# tap_test.net
KiCad netlist of a schematic drawn in EAGLE
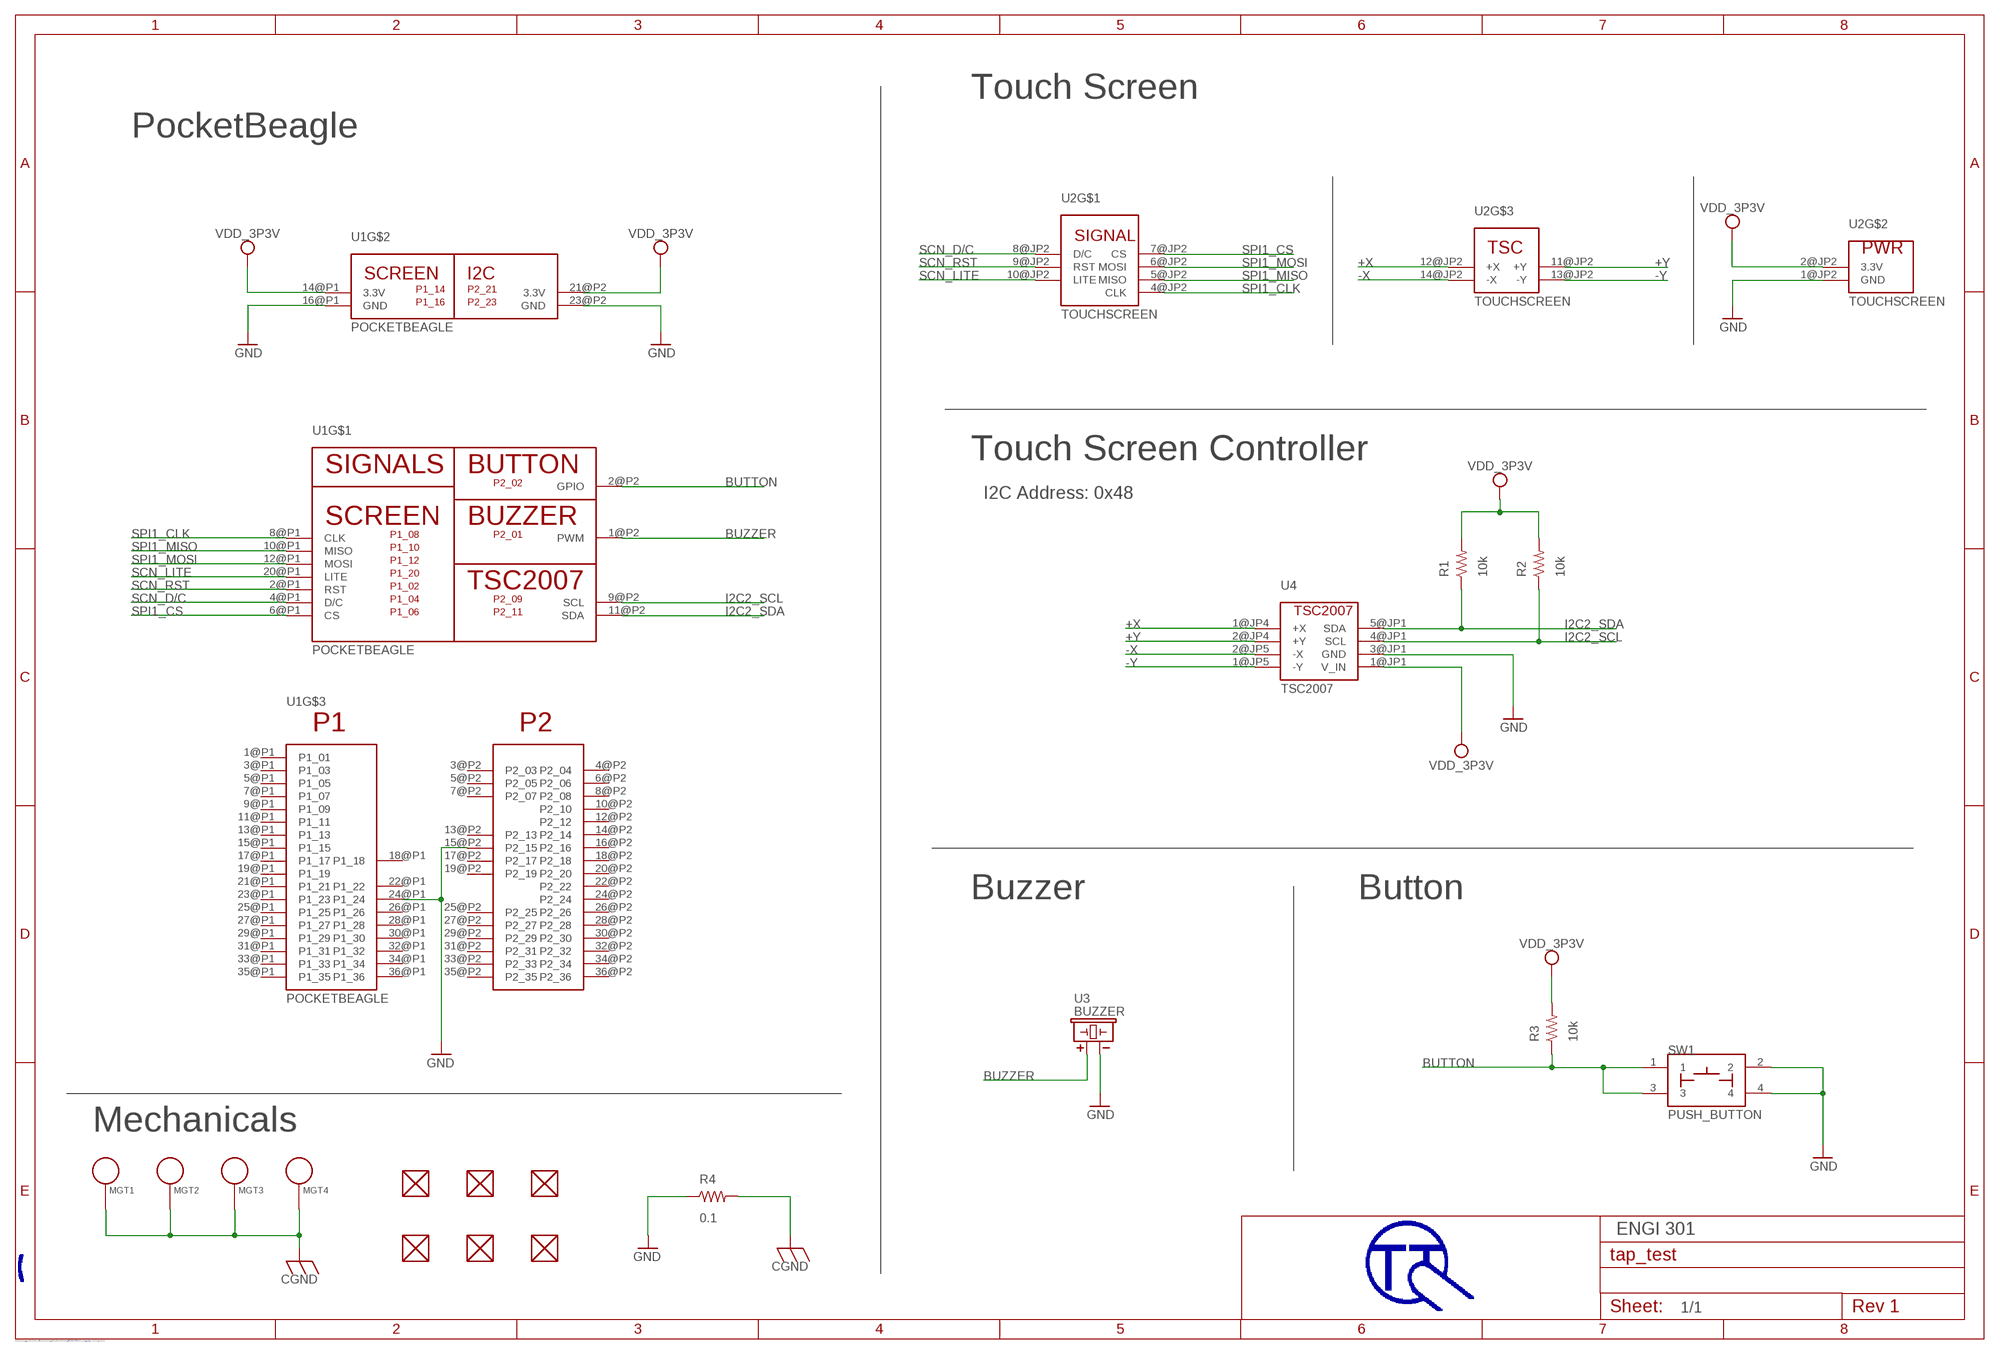
[diagram p0: schematic, sheet 1]

(export (version "E")
  (design (tool "Eeschema 10.0.6"))
  (components
    (comp (ref "FUD1")
      (value "FIDUCIAL")
      (footprint "eagle-import:FIDUCIAL_40MIL")
      (libsource (lib "eagle-import") (part "FIDUCIAL"))
    )
    (comp (ref "FUD2")
      (value "FIDUCIAL")
      (footprint "eagle-import:FIDUCIAL_40MIL")
      (libsource (lib "eagle-import") (part "FIDUCIAL"))
    )
    (comp (ref "FUD3")
      (value "FIDUCIAL")
      (footprint "eagle-import:FIDUCIAL_40MIL")
      (libsource (lib "eagle-import") (part "FIDUCIAL"))
    )
    (comp (ref "FUD4")
      (value "FIDUCIAL")
      (footprint "eagle-import:FIDUCIAL_40MIL")
      (libsource (lib "eagle-import") (part "FIDUCIAL"))
    )
    (comp (ref "FUD5")
      (value "FIDUCIAL")
      (footprint "eagle-import:FIDUCIAL_40MIL")
      (libsource (lib "eagle-import") (part "FIDUCIAL"))
    )
    (comp (ref "FUD6")
      (value "FIDUCIAL")
      (footprint "eagle-import:FIDUCIAL_40MIL")
      (libsource (lib "eagle-import") (part "FIDUCIAL"))
    )
    (comp (ref "MGT1")
      (value "MOUNTING_HOLE")
      (footprint "eagle-import:MOUNTING_HOLE")
      (libsource (lib "eagle-import") (part "MOUNTING_HOLE"))
    )
    (comp (ref "MGT2")
      (value "MOUNTING_HOLE")
      (footprint "eagle-import:MOUNTING_HOLE")
      (libsource (lib "eagle-import") (part "MOUNTING_HOLE"))
    )
    (comp (ref "MGT3")
      (value "MOUNTING_HOLE")
      (footprint "eagle-import:MOUNTING_HOLE")
      (libsource (lib "eagle-import") (part "MOUNTING_HOLE"))
    )
    (comp (ref "MGT4")
      (value "MOUNTING_HOLE")
      (footprint "eagle-import:MOUNTING_HOLE")
      (libsource (lib "eagle-import") (part "MOUNTING_HOLE"))
    )
    (comp (ref "R1")
      (value "10k")
      (footprint "eagle-import:R0603")
      (libsource (lib "eagle-import") (part "R_R0603"))
    )
    (comp (ref "R2")
      (value "10k")
      (footprint "eagle-import:R0603")
      (libsource (lib "eagle-import") (part "R_R0603"))
    )
    (comp (ref "R3")
      (value "10k")
      (footprint "eagle-import:R0603")
      (libsource (lib "eagle-import") (part "R_R0603"))
    )
    (comp (ref "R4")
      (value "0.1")
      (footprint "eagle-import:R0603")
      (libsource (lib "eagle-import") (part "R_R0603"))
    )
    (comp (ref "SW1")
      (value "PUSH_BUTTON")
      (footprint "eagle-import:BUTTON_12.5MM")
      (libsource (lib "eagle-import") (part "PUSH_BUTTON"))
    )
    (comp (ref "U1")
      (value "POCKETBEAGLE")
      (footprint "eagle-import:POCKETBEAGLE")
      (libsource (lib "eagle-import") (part "POCKETBEAGLE"))
    )
    (comp (ref "U2")
      (value "TOUCHSCREEN")
      (footprint "eagle-import:TOUCHSCREEN")
      (libsource (lib "eagle-import") (part "TOUCHSCREEN"))
    )
    (comp (ref "U3")
      (value "BUZZER")
      (footprint "eagle-import:BUZZER_6.5MM")
      (libsource (lib "eagle-import") (part "BUZZER"))
    )
    (comp (ref "U4")
      (value "TSC2007")
      (footprint "eagle-import:TSC2007")
      (libsource (lib "eagle-import") (part "TSC2007"))
    )
  )
  (nets
    (net (code "1") (name "/+X") (class "Default")
      (node (ref "U2") (pin "12@JP2") (pinfunction "+X_12@JP2") (pintype "bidirectional"))
      (node (ref "U4") (pin "1@JP4") (pinfunction "+X_1@JP4") (pintype "bidirectional"))
    )
    (net (code "2") (name "/+Y") (class "Default")
      (node (ref "U2") (pin "11@JP2") (pinfunction "+Y_11@JP2") (pintype "bidirectional"))
      (node (ref "U4") (pin "2@JP4") (pinfunction "+Y_2@JP4") (pintype "bidirectional"))
    )
    (net (code "3") (name "/-X") (class "Default")
      (node (ref "U2") (pin "14@JP2") (pinfunction "-X_14@JP2") (pintype "bidirectional"))
      (node (ref "U4") (pin "2@JP5") (pinfunction "-X_2@JP5") (pintype "bidirectional"))
    )
    (net (code "4") (name "/-Y") (class "Default")
      (node (ref "U2") (pin "13@JP2") (pinfunction "-Y_13@JP2") (pintype "bidirectional"))
      (node (ref "U4") (pin "1@JP5") (pinfunction "-Y_1@JP5") (pintype "bidirectional"))
    )
    (net (code "5") (name "/BUTTON") (class "Default")
      (node (ref "R3") (pin "1") (pinfunction "1_1") (pintype "passive"))
      (node (ref "SW1") (pin "1") (pinfunction "1_1") (pintype "bidirectional"))
      (node (ref "SW1") (pin "3") (pinfunction "3_3") (pintype "bidirectional"))
      (node (ref "U1") (pin "2@P2") (pinfunction "GPIO_2@P2") (pintype "bidirectional"))
    )
    (net (code "6") (name "/BUZZER") (class "Default")
      (node (ref "U1") (pin "1@P2") (pinfunction "PWM_1@P2") (pintype "bidirectional"))
      (node (ref "U3") (pin "+") (pinfunction "+_+") (pintype "passive"))
    )
    (net (code "7") (name "/I2C2_SCL") (class "Default")
      (node (ref "R2") (pin "1") (pinfunction "1_1") (pintype "passive"))
      (node (ref "U1") (pin "9@P2") (pinfunction "SCL_9@P2") (pintype "bidirectional"))
      (node (ref "U4") (pin "4@JP1") (pinfunction "SCL_4@JP1") (pintype "bidirectional"))
    )
    (net (code "8") (name "/I2C2_SDA") (class "Default")
      (node (ref "R1") (pin "1") (pinfunction "1_1") (pintype "passive"))
      (node (ref "U1") (pin "11@P2") (pinfunction "SDA_11@P2") (pintype "bidirectional"))
      (node (ref "U4") (pin "5@JP1") (pinfunction "SDA_5@JP1") (pintype "bidirectional"))
    )
    (net (code "9") (name "/SCN_D{slash}C") (class "Default")
      (node (ref "U1") (pin "4@P1") (pinfunction "D/C_4@P1") (pintype "bidirectional"))
      (node (ref "U2") (pin "8@JP2") (pinfunction "D/C_8@JP2") (pintype "bidirectional"))
    )
    (net (code "10") (name "/SCN_LITE") (class "Default")
      (node (ref "U1") (pin "20@P1") (pinfunction "LITE_20@P1") (pintype "bidirectional"))
      (node (ref "U2") (pin "10@JP2") (pinfunction "LITE_10@JP2") (pintype "bidirectional"))
    )
    (net (code "11") (name "/SCN_RST") (class "Default")
      (node (ref "U1") (pin "2@P1") (pinfunction "RST_2@P1") (pintype "bidirectional"))
      (node (ref "U2") (pin "9@JP2") (pinfunction "RST_9@JP2") (pintype "bidirectional"))
    )
    (net (code "12") (name "/SPI1_CLK") (class "Default")
      (node (ref "U1") (pin "8@P1") (pinfunction "CLK_8@P1") (pintype "bidirectional"))
      (node (ref "U2") (pin "4@JP2") (pinfunction "CLK_4@JP2") (pintype "bidirectional"))
    )
    (net (code "13") (name "/SPI1_CS") (class "Default")
      (node (ref "U1") (pin "6@P1") (pinfunction "CS_6@P1") (pintype "bidirectional"))
      (node (ref "U2") (pin "7@JP2") (pinfunction "CS_7@JP2") (pintype "bidirectional"))
    )
    (net (code "14") (name "/SPI1_MISO") (class "Default")
      (node (ref "U1") (pin "10@P1") (pinfunction "MISO_10@P1") (pintype "bidirectional"))
      (node (ref "U2") (pin "5@JP2") (pinfunction "MISO_5@JP2") (pintype "bidirectional"))
    )
    (net (code "15") (name "/SPI1_MOSI") (class "Default")
      (node (ref "U1") (pin "12@P1") (pinfunction "MOSI_12@P1") (pintype "bidirectional"))
      (node (ref "U2") (pin "6@JP2") (pinfunction "MOSI_6@JP2") (pintype "bidirectional"))
    )
    (net (code "16") (name "CGND") (class "Default")
      (node (ref "MGT1") (pin "P$1") (pinfunction "P$1_P$1") (pintype "bidirectional"))
      (node (ref "MGT2") (pin "P$1") (pinfunction "P$1_P$1") (pintype "bidirectional"))
      (node (ref "MGT3") (pin "P$1") (pinfunction "P$1_P$1") (pintype "bidirectional"))
      (node (ref "MGT4") (pin "P$1") (pinfunction "P$1_P$1") (pintype "bidirectional"))
      (node (ref "R4") (pin "2") (pinfunction "2_2") (pintype "passive"))
    )
    (net (code "17") (name "GND") (class "Default")
      (node (ref "R4") (pin "1") (pinfunction "1_1") (pintype "passive"))
      (node (ref "SW1") (pin "2") (pinfunction "2_2") (pintype "bidirectional"))
      (node (ref "SW1") (pin "4") (pinfunction "4_4") (pintype "bidirectional"))
      (node (ref "U1") (pin "15@P2") (pinfunction "P2_15_15@P2") (pintype "bidirectional"))
      (node (ref "U1") (pin "16@P1") (pinfunction "GND_16@P1") (pintype "bidirectional"))
      (node (ref "U1") (pin "23@P2") (pinfunction "GND_23@P2") (pintype "bidirectional"))
      (node (ref "U1") (pin "24@P1") (pinfunction "P1_24_24@P1") (pintype "bidirectional"))
      (node (ref "U2") (pin "1@JP2") (pinfunction "GND_1@JP2") (pintype "bidirectional"))
      (node (ref "U3") (pin "-") (pinfunction "-_-") (pintype "passive"))
      (node (ref "U4") (pin "3@JP1") (pinfunction "GND_3@JP1") (pintype "bidirectional"))
    )
    (net (code "18") (name "VDD_3P3V") (class "Default")
      (node (ref "R1") (pin "2") (pinfunction "2_2") (pintype "passive"))
      (node (ref "R2") (pin "2") (pinfunction "2_2") (pintype "passive"))
      (node (ref "R3") (pin "2") (pinfunction "2_2") (pintype "passive"))
      (node (ref "U1") (pin "14@P1") (pinfunction "3.3V_14@P1") (pintype "bidirectional"))
      (node (ref "U1") (pin "21@P2") (pinfunction "3.3V_21@P2") (pintype "bidirectional"))
      (node (ref "U2") (pin "2@JP2") (pinfunction "3.3V_2@JP2") (pintype "bidirectional"))
      (node (ref "U4") (pin "1@JP1") (pinfunction "V_IN_1@JP1") (pintype "bidirectional"))
    )
    (net (code "19") (name "unconnected-(FUD1-PadP$1)") (class "Default")
      (node (ref "FUD1") (pin "P$1") (pinfunction "P$1_P$1") (pintype "no_connect"))
    )
    (net (code "20") (name "unconnected-(FUD2-PadP$1)") (class "Default")
      (node (ref "FUD2") (pin "P$1") (pinfunction "P$1_P$1") (pintype "no_connect"))
    )
    (net (code "21") (name "unconnected-(FUD3-PadP$1)") (class "Default")
      (node (ref "FUD3") (pin "P$1") (pinfunction "P$1_P$1") (pintype "no_connect"))
    )
    (net (code "22") (name "unconnected-(FUD4-PadP$1)") (class "Default")
      (node (ref "FUD4") (pin "P$1") (pinfunction "P$1_P$1") (pintype "no_connect"))
    )
    (net (code "23") (name "unconnected-(FUD5-PadP$1)") (class "Default")
      (node (ref "FUD5") (pin "P$1") (pinfunction "P$1_P$1") (pintype "no_connect"))
    )
    (net (code "24") (name "unconnected-(FUD6-PadP$1)") (class "Default")
      (node (ref "FUD6") (pin "P$1") (pinfunction "P$1_P$1") (pintype "no_connect"))
    )
    (net (code "25") (name "unconnected-(U1C-P1_01-Pad1@P1)") (class "Default")
      (node (ref "U1") (pin "1@P1") (pinfunction "P1_01_1@P1") (pintype "bidirectional"))
    )
    (net (code "26") (name "unconnected-(U1C-P1_03-Pad3@P1)") (class "Default")
      (node (ref "U1") (pin "3@P1") (pinfunction "P1_03_3@P1") (pintype "bidirectional"))
    )
    (net (code "27") (name "unconnected-(U1C-P1_05-Pad5@P1)") (class "Default")
      (node (ref "U1") (pin "5@P1") (pinfunction "P1_05_5@P1") (pintype "bidirectional"))
    )
    (net (code "28") (name "unconnected-(U1C-P1_07-Pad7@P1)") (class "Default")
      (node (ref "U1") (pin "7@P1") (pinfunction "P1_07_7@P1") (pintype "bidirectional"))
    )
    (net (code "29") (name "unconnected-(U1C-P1_09-Pad9@P1)") (class "Default")
      (node (ref "U1") (pin "9@P1") (pinfunction "P1_09_9@P1") (pintype "bidirectional"))
    )
    (net (code "30") (name "unconnected-(U1C-P1_11-Pad11@P1)") (class "Default")
      (node (ref "U1") (pin "11@P1") (pinfunction "P1_11_11@P1") (pintype "bidirectional"))
    )
    (net (code "31") (name "unconnected-(U1C-P1_13-Pad13@P1)") (class "Default")
      (node (ref "U1") (pin "13@P1") (pinfunction "P1_13_13@P1") (pintype "bidirectional"))
    )
    (net (code "32") (name "unconnected-(U1C-P1_15-Pad15@P1)") (class "Default")
      (node (ref "U1") (pin "15@P1") (pinfunction "P1_15_15@P1") (pintype "bidirectional"))
    )
    (net (code "33") (name "unconnected-(U1C-P1_17-Pad17@P1)") (class "Default")
      (node (ref "U1") (pin "17@P1") (pinfunction "P1_17_17@P1") (pintype "bidirectional"))
    )
    (net (code "34") (name "unconnected-(U1C-P1_18-Pad18@P1)") (class "Default")
      (node (ref "U1") (pin "18@P1") (pinfunction "P1_18_18@P1") (pintype "bidirectional"))
    )
    (net (code "35") (name "unconnected-(U1C-P1_19-Pad19@P1)") (class "Default")
      (node (ref "U1") (pin "19@P1") (pinfunction "P1_19_19@P1") (pintype "bidirectional"))
    )
    (net (code "36") (name "unconnected-(U1C-P1_21-Pad21@P1)") (class "Default")
      (node (ref "U1") (pin "21@P1") (pinfunction "P1_21_21@P1") (pintype "bidirectional"))
    )
    (net (code "37") (name "unconnected-(U1C-P1_22-Pad22@P1)") (class "Default")
      (node (ref "U1") (pin "22@P1") (pinfunction "P1_22_22@P1") (pintype "bidirectional"))
    )
    (net (code "38") (name "unconnected-(U1C-P1_23-Pad23@P1)") (class "Default")
      (node (ref "U1") (pin "23@P1") (pinfunction "P1_23_23@P1") (pintype "bidirectional"))
    )
    (net (code "39") (name "unconnected-(U1C-P1_25-Pad25@P1)") (class "Default")
      (node (ref "U1") (pin "25@P1") (pinfunction "P1_25_25@P1") (pintype "bidirectional"))
    )
    (net (code "40") (name "unconnected-(U1C-P1_26-Pad26@P1)") (class "Default")
      (node (ref "U1") (pin "26@P1") (pinfunction "P1_26_26@P1") (pintype "bidirectional"))
    )
    (net (code "41") (name "unconnected-(U1C-P1_27-Pad27@P1)") (class "Default")
      (node (ref "U1") (pin "27@P1") (pinfunction "P1_27_27@P1") (pintype "bidirectional"))
    )
    (net (code "42") (name "unconnected-(U1C-P1_28-Pad28@P1)") (class "Default")
      (node (ref "U1") (pin "28@P1") (pinfunction "P1_28_28@P1") (pintype "bidirectional"))
    )
    (net (code "43") (name "unconnected-(U1C-P1_29-Pad29@P1)") (class "Default")
      (node (ref "U1") (pin "29@P1") (pinfunction "P1_29_29@P1") (pintype "bidirectional"))
    )
    (net (code "44") (name "unconnected-(U1C-P1_30-Pad30@P1)") (class "Default")
      (node (ref "U1") (pin "30@P1") (pinfunction "P1_30_30@P1") (pintype "bidirectional"))
    )
    (net (code "45") (name "unconnected-(U1C-P1_31-Pad31@P1)") (class "Default")
      (node (ref "U1") (pin "31@P1") (pinfunction "P1_31_31@P1") (pintype "bidirectional"))
    )
    (net (code "46") (name "unconnected-(U1C-P1_32-Pad32@P1)") (class "Default")
      (node (ref "U1") (pin "32@P1") (pinfunction "P1_32_32@P1") (pintype "bidirectional"))
    )
    (net (code "47") (name "unconnected-(U1C-P1_33-Pad33@P1)") (class "Default")
      (node (ref "U1") (pin "33@P1") (pinfunction "P1_33_33@P1") (pintype "bidirectional"))
    )
    (net (code "48") (name "unconnected-(U1C-P1_34-Pad34@P1)") (class "Default")
      (node (ref "U1") (pin "34@P1") (pinfunction "P1_34_34@P1") (pintype "bidirectional"))
    )
    (net (code "49") (name "unconnected-(U1C-P1_35-Pad35@P1)") (class "Default")
      (node (ref "U1") (pin "35@P1") (pinfunction "P1_35_35@P1") (pintype "bidirectional"))
    )
    (net (code "50") (name "unconnected-(U1C-P1_36-Pad36@P1)") (class "Default")
      (node (ref "U1") (pin "36@P1") (pinfunction "P1_36_36@P1") (pintype "bidirectional"))
    )
    (net (code "51") (name "unconnected-(U1C-P2_03-Pad3@P2)") (class "Default")
      (node (ref "U1") (pin "3@P2") (pinfunction "P2_03_3@P2") (pintype "bidirectional"))
    )
    (net (code "52") (name "unconnected-(U1C-P2_04-Pad4@P2)") (class "Default")
      (node (ref "U1") (pin "4@P2") (pinfunction "P2_04_4@P2") (pintype "bidirectional"))
    )
    (net (code "53") (name "unconnected-(U1C-P2_05-Pad5@P2)") (class "Default")
      (node (ref "U1") (pin "5@P2") (pinfunction "P2_05_5@P2") (pintype "bidirectional"))
    )
    (net (code "54") (name "unconnected-(U1C-P2_06-Pad6@P2)") (class "Default")
      (node (ref "U1") (pin "6@P2") (pinfunction "P2_06_6@P2") (pintype "bidirectional"))
    )
    (net (code "55") (name "unconnected-(U1C-P2_07-Pad7@P2)") (class "Default")
      (node (ref "U1") (pin "7@P2") (pinfunction "P2_07_7@P2") (pintype "bidirectional"))
    )
    (net (code "56") (name "unconnected-(U1C-P2_08-Pad8@P2)") (class "Default")
      (node (ref "U1") (pin "8@P2") (pinfunction "P2_08_8@P2") (pintype "bidirectional"))
    )
    (net (code "57") (name "unconnected-(U1C-P2_10-Pad10@P2)") (class "Default")
      (node (ref "U1") (pin "10@P2") (pinfunction "P2_10_10@P2") (pintype "bidirectional"))
    )
    (net (code "58") (name "unconnected-(U1C-P2_12-Pad12@P2)") (class "Default")
      (node (ref "U1") (pin "12@P2") (pinfunction "P2_12_12@P2") (pintype "bidirectional"))
    )
    (net (code "59") (name "unconnected-(U1C-P2_13-Pad13@P2)") (class "Default")
      (node (ref "U1") (pin "13@P2") (pinfunction "P2_13_13@P2") (pintype "bidirectional"))
    )
    (net (code "60") (name "unconnected-(U1C-P2_14-Pad14@P2)") (class "Default")
      (node (ref "U1") (pin "14@P2") (pinfunction "P2_14_14@P2") (pintype "bidirectional"))
    )
    (net (code "61") (name "unconnected-(U1C-P2_16-Pad16@P2)") (class "Default")
      (node (ref "U1") (pin "16@P2") (pinfunction "P2_16_16@P2") (pintype "bidirectional"))
    )
    (net (code "62") (name "unconnected-(U1C-P2_17-Pad17@P2)") (class "Default")
      (node (ref "U1") (pin "17@P2") (pinfunction "P2_17_17@P2") (pintype "bidirectional"))
    )
    (net (code "63") (name "unconnected-(U1C-P2_18-Pad18@P2)") (class "Default")
      (node (ref "U1") (pin "18@P2") (pinfunction "P2_18_18@P2") (pintype "bidirectional"))
    )
    (net (code "64") (name "unconnected-(U1C-P2_19-Pad19@P2)") (class "Default")
      (node (ref "U1") (pin "19@P2") (pinfunction "P2_19_19@P2") (pintype "bidirectional"))
    )
    (net (code "65") (name "unconnected-(U1C-P2_20-Pad20@P2)") (class "Default")
      (node (ref "U1") (pin "20@P2") (pinfunction "P2_20_20@P2") (pintype "bidirectional"))
    )
    (net (code "66") (name "unconnected-(U1C-P2_22-Pad22@P2)") (class "Default")
      (node (ref "U1") (pin "22@P2") (pinfunction "P2_22_22@P2") (pintype "bidirectional"))
    )
    (net (code "67") (name "unconnected-(U1C-P2_24-Pad24@P2)") (class "Default")
      (node (ref "U1") (pin "24@P2") (pinfunction "P2_24_24@P2") (pintype "bidirectional"))
    )
    (net (code "68") (name "unconnected-(U1C-P2_25-Pad25@P2)") (class "Default")
      (node (ref "U1") (pin "25@P2") (pinfunction "P2_25_25@P2") (pintype "bidirectional"))
    )
    (net (code "69") (name "unconnected-(U1C-P2_26-Pad26@P2)") (class "Default")
      (node (ref "U1") (pin "26@P2") (pinfunction "P2_26_26@P2") (pintype "bidirectional"))
    )
    (net (code "70") (name "unconnected-(U1C-P2_27-Pad27@P2)") (class "Default")
      (node (ref "U1") (pin "27@P2") (pinfunction "P2_27_27@P2") (pintype "bidirectional"))
    )
    (net (code "71") (name "unconnected-(U1C-P2_28-Pad28@P2)") (class "Default")
      (node (ref "U1") (pin "28@P2") (pinfunction "P2_28_28@P2") (pintype "bidirectional"))
    )
    (net (code "72") (name "unconnected-(U1C-P2_29-Pad29@P2)") (class "Default")
      (node (ref "U1") (pin "29@P2") (pinfunction "P2_29_29@P2") (pintype "bidirectional"))
    )
    (net (code "73") (name "unconnected-(U1C-P2_30-Pad30@P2)") (class "Default")
      (node (ref "U1") (pin "30@P2") (pinfunction "P2_30_30@P2") (pintype "bidirectional"))
    )
    (net (code "74") (name "unconnected-(U1C-P2_31-Pad31@P2)") (class "Default")
      (node (ref "U1") (pin "31@P2") (pinfunction "P2_31_31@P2") (pintype "bidirectional"))
    )
    (net (code "75") (name "unconnected-(U1C-P2_32-Pad32@P2)") (class "Default")
      (node (ref "U1") (pin "32@P2") (pinfunction "P2_32_32@P2") (pintype "bidirectional"))
    )
    (net (code "76") (name "unconnected-(U1C-P2_33-Pad33@P2)") (class "Default")
      (node (ref "U1") (pin "33@P2") (pinfunction "P2_33_33@P2") (pintype "bidirectional"))
    )
    (net (code "77") (name "unconnected-(U1C-P2_34-Pad34@P2)") (class "Default")
      (node (ref "U1") (pin "34@P2") (pinfunction "P2_34_34@P2") (pintype "bidirectional"))
    )
    (net (code "78") (name "unconnected-(U1C-P2_35-Pad35@P2)") (class "Default")
      (node (ref "U1") (pin "35@P2") (pinfunction "P2_35_35@P2") (pintype "bidirectional"))
    )
    (net (code "79") (name "unconnected-(U1C-P2_36-Pad36@P2)") (class "Default")
      (node (ref "U1") (pin "36@P2") (pinfunction "P2_36_36@P2") (pintype "bidirectional"))
    )
  )
)
